# scarab-trigger-shield-bb.net
KiCad netlist of a schematic drawn in EAGLE
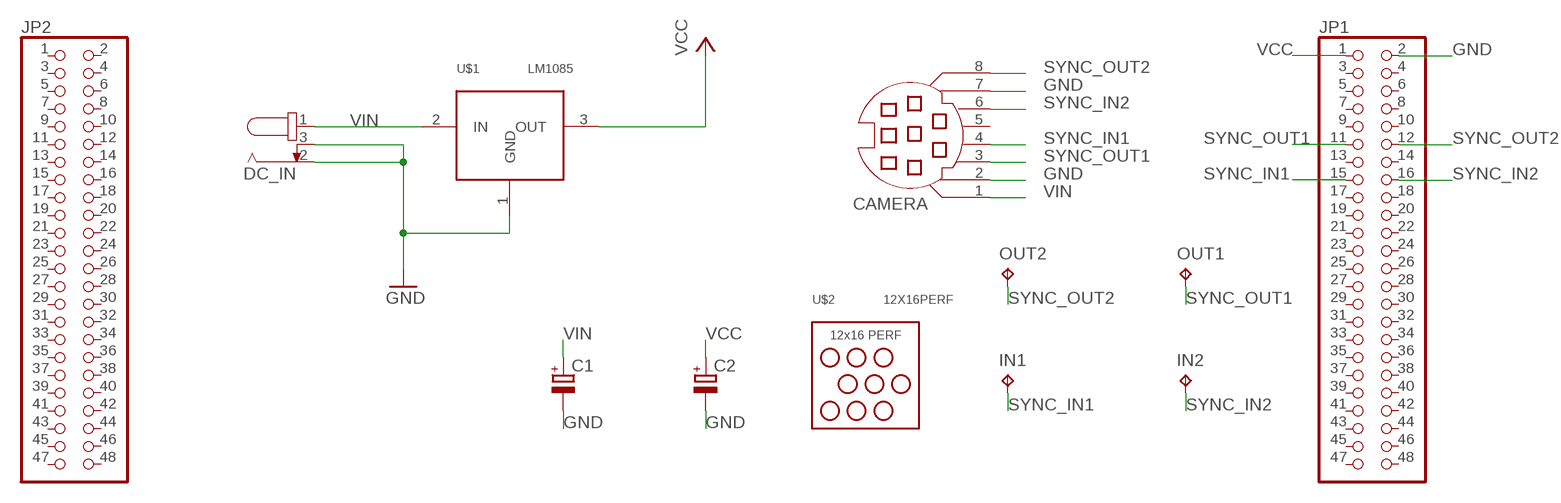
[diagram p0: schematic, sheet 1]

(export (version "E")
  (design (tool "Eeschema 10.0.6"))
  (components
    (comp (ref "C1")
      (value "CPOL-EUCT7343")
      (footprint "eagle-import:CT7343")
      (libsource (lib "eagle-import") (part "CPOL-EUCT7343"))
    )
    (comp (ref "C2")
      (value "CPOL-EUCT7343")
      (footprint "eagle-import:CT7343")
      (libsource (lib "eagle-import") (part "CPOL-EUCT7343"))
    )
    (comp (ref "CAMERA")
      (value "MD08SS")
      (footprint "eagle-import:MDIN08SS")
      (libsource (lib "eagle-import") (part "MD08SS"))
    )
    (comp (ref "DC_IN")
      (value "694106105102")
      (footprint "eagle-import:694106105102")
      (libsource (lib "eagle-import") (part "694106105102"))
    )
    (comp (ref "IN1")
      (value "TPTP20R")
      (footprint "eagle-import:TP20R")
      (libsource (lib "eagle-import") (part "TPTP20R"))
    )
    (comp (ref "IN2")
      (value "TPTP20R")
      (footprint "eagle-import:TP20R")
      (libsource (lib "eagle-import") (part "TPTP20R"))
    )
    (comp (ref "JP1")
      (value "PINHD-2X24")
      (footprint "eagle-import:2X24")
      (libsource (lib "eagle-import") (part "PINHD-2X24"))
    )
    (comp (ref "JP2")
      (value "PINHD-2X24")
      (footprint "eagle-import:2X24")
      (libsource (lib "eagle-import") (part "PINHD-2X24"))
    )
    (comp (ref "OUT1")
      (value "TPTP20R")
      (footprint "eagle-import:TP20R")
      (libsource (lib "eagle-import") (part "TPTP20R"))
    )
    (comp (ref "OUT2")
      (value "TPTP20R")
      (footprint "eagle-import:TP20R")
      (libsource (lib "eagle-import") (part "TPTP20R"))
    )
    (comp (ref "U$1")
      (value "LM1085")
      (footprint "eagle-import:TO263")
      (libsource (lib "eagle-import") (part "LM1085"))
    )
    (comp (ref "U$2")
      (value "12X16PERF")
      (footprint "eagle-import:PERF-GRID")
      (libsource (lib "eagle-import") (part "12X16PERF"))
    )
  )
  (nets
    (net (code "1") (name "/SYNC_IN1") (class "Default")
      (node (ref "CAMERA") (pin "4") (pinfunction "4_4") (pintype "passive"))
      (node (ref "IN1") (pin "TP") (pinfunction "TP_TP") (pintype "input"))
      (node (ref "JP1") (pin "15") (pinfunction "15_15") (pintype "passive"))
    )
    (net (code "2") (name "/SYNC_IN2") (class "Default")
      (node (ref "CAMERA") (pin "6") (pinfunction "6_6") (pintype "passive"))
      (node (ref "IN2") (pin "TP") (pinfunction "TP_TP") (pintype "input"))
      (node (ref "JP1") (pin "16") (pinfunction "16_16") (pintype "passive"))
    )
    (net (code "3") (name "/SYNC_OUT1") (class "Default")
      (node (ref "CAMERA") (pin "3") (pinfunction "3_3") (pintype "passive"))
      (node (ref "JP1") (pin "11") (pinfunction "11_11") (pintype "passive"))
      (node (ref "OUT1") (pin "TP") (pinfunction "TP_TP") (pintype "input"))
    )
    (net (code "4") (name "/SYNC_OUT2") (class "Default")
      (node (ref "CAMERA") (pin "8") (pinfunction "8_8") (pintype "passive"))
      (node (ref "JP1") (pin "12") (pinfunction "12_12") (pintype "passive"))
      (node (ref "OUT2") (pin "TP") (pinfunction "TP_TP") (pintype "input"))
    )
    (net (code "5") (name "/VIN") (class "Default")
      (node (ref "C1") (pin "+") (pinfunction "+_+") (pintype "passive"))
      (node (ref "CAMERA") (pin "1") (pinfunction "1_1") (pintype "passive"))
      (node (ref "DC_IN") (pin "1") (pinfunction "1_1") (pintype "passive"))
      (node (ref "U$1") (pin "2") (pinfunction "IN_2") (pintype "bidirectional"))
    )
    (net (code "6") (name "GND") (class "Default")
      (node (ref "C1") (pin "-") (pinfunction "-_-") (pintype "passive"))
      (node (ref "C2") (pin "-") (pinfunction "-_-") (pintype "passive"))
      (node (ref "CAMERA") (pin "2") (pinfunction "2_2") (pintype "passive"))
      (node (ref "CAMERA") (pin "7") (pinfunction "7_7") (pintype "passive"))
      (node (ref "DC_IN") (pin "2") (pinfunction "2_2") (pintype "passive"))
      (node (ref "DC_IN") (pin "3") (pinfunction "3_3") (pintype "passive"))
      (node (ref "JP1") (pin "2") (pinfunction "2_2") (pintype "passive"))
      (node (ref "U$1") (pin "1") (pinfunction "GND_1") (pintype "bidirectional"))
    )
    (net (code "7") (name "VCC") (class "Default")
      (node (ref "C2") (pin "+") (pinfunction "+_+") (pintype "passive"))
      (node (ref "JP1") (pin "1") (pinfunction "1_1") (pintype "passive"))
      (node (ref "U$1") (pin "3") (pinfunction "OUT_3") (pintype "bidirectional"))
    )
    (net (code "8") (name "unconnected-(CAMERA-Pad5)") (class "Default")
      (node (ref "CAMERA") (pin "5") (pinfunction "5_5") (pintype "passive"))
    )
    (net (code "9") (name "unconnected-(JP1-Pad3)") (class "Default")
      (node (ref "JP1") (pin "3") (pinfunction "3_3") (pintype "passive"))
    )
    (net (code "10") (name "unconnected-(JP1-Pad4)") (class "Default")
      (node (ref "JP1") (pin "4") (pinfunction "4_4") (pintype "passive"))
    )
    (net (code "11") (name "unconnected-(JP1-Pad5)") (class "Default")
      (node (ref "JP1") (pin "5") (pinfunction "5_5") (pintype "passive"))
    )
    (net (code "12") (name "unconnected-(JP1-Pad6)") (class "Default")
      (node (ref "JP1") (pin "6") (pinfunction "6_6") (pintype "passive"))
    )
    (net (code "13") (name "unconnected-(JP1-Pad7)") (class "Default")
      (node (ref "JP1") (pin "7") (pinfunction "7_7") (pintype "passive"))
    )
    (net (code "14") (name "unconnected-(JP1-Pad8)") (class "Default")
      (node (ref "JP1") (pin "8") (pinfunction "8_8") (pintype "passive"))
    )
    (net (code "15") (name "unconnected-(JP1-Pad9)") (class "Default")
      (node (ref "JP1") (pin "9") (pinfunction "9_9") (pintype "passive"))
    )
    (net (code "16") (name "unconnected-(JP1-Pad10)") (class "Default")
      (node (ref "JP1") (pin "10") (pinfunction "10_10") (pintype "passive"))
    )
    (net (code "17") (name "unconnected-(JP1-Pad13)") (class "Default")
      (node (ref "JP1") (pin "13") (pinfunction "13_13") (pintype "passive"))
    )
    (net (code "18") (name "unconnected-(JP1-Pad14)") (class "Default")
      (node (ref "JP1") (pin "14") (pinfunction "14_14") (pintype "passive"))
    )
    (net (code "19") (name "unconnected-(JP1-Pad17)") (class "Default")
      (node (ref "JP1") (pin "17") (pinfunction "17_17") (pintype "passive"))
    )
    (net (code "20") (name "unconnected-(JP1-Pad18)") (class "Default")
      (node (ref "JP1") (pin "18") (pinfunction "18_18") (pintype "passive"))
    )
    (net (code "21") (name "unconnected-(JP1-Pad19)") (class "Default")
      (node (ref "JP1") (pin "19") (pinfunction "19_19") (pintype "passive"))
    )
    (net (code "22") (name "unconnected-(JP1-Pad20)") (class "Default")
      (node (ref "JP1") (pin "20") (pinfunction "20_20") (pintype "passive"))
    )
    (net (code "23") (name "unconnected-(JP1-Pad21)") (class "Default")
      (node (ref "JP1") (pin "21") (pinfunction "21_21") (pintype "passive"))
    )
    (net (code "24") (name "unconnected-(JP1-Pad22)") (class "Default")
      (node (ref "JP1") (pin "22") (pinfunction "22_22") (pintype "passive"))
    )
    (net (code "25") (name "unconnected-(JP1-Pad23)") (class "Default")
      (node (ref "JP1") (pin "23") (pinfunction "23_23") (pintype "passive"))
    )
    (net (code "26") (name "unconnected-(JP1-Pad24)") (class "Default")
      (node (ref "JP1") (pin "24") (pinfunction "24_24") (pintype "passive"))
    )
    (net (code "27") (name "unconnected-(JP1-Pad25)") (class "Default")
      (node (ref "JP1") (pin "25") (pinfunction "25_25") (pintype "passive"))
    )
    (net (code "28") (name "unconnected-(JP1-Pad26)") (class "Default")
      (node (ref "JP1") (pin "26") (pinfunction "26_26") (pintype "passive"))
    )
    (net (code "29") (name "unconnected-(JP1-Pad27)") (class "Default")
      (node (ref "JP1") (pin "27") (pinfunction "27_27") (pintype "passive"))
    )
    (net (code "30") (name "unconnected-(JP1-Pad28)") (class "Default")
      (node (ref "JP1") (pin "28") (pinfunction "28_28") (pintype "passive"))
    )
    (net (code "31") (name "unconnected-(JP1-Pad29)") (class "Default")
      (node (ref "JP1") (pin "29") (pinfunction "29_29") (pintype "passive"))
    )
    (net (code "32") (name "unconnected-(JP1-Pad30)") (class "Default")
      (node (ref "JP1") (pin "30") (pinfunction "30_30") (pintype "passive"))
    )
    (net (code "33") (name "unconnected-(JP1-Pad31)") (class "Default")
      (node (ref "JP1") (pin "31") (pinfunction "31_31") (pintype "passive"))
    )
    (net (code "34") (name "unconnected-(JP1-Pad32)") (class "Default")
      (node (ref "JP1") (pin "32") (pinfunction "32_32") (pintype "passive"))
    )
    (net (code "35") (name "unconnected-(JP1-Pad33)") (class "Default")
      (node (ref "JP1") (pin "33") (pinfunction "33_33") (pintype "passive"))
    )
    (net (code "36") (name "unconnected-(JP1-Pad34)") (class "Default")
      (node (ref "JP1") (pin "34") (pinfunction "34_34") (pintype "passive"))
    )
    (net (code "37") (name "unconnected-(JP1-Pad35)") (class "Default")
      (node (ref "JP1") (pin "35") (pinfunction "35_35") (pintype "passive"))
    )
    (net (code "38") (name "unconnected-(JP1-Pad36)") (class "Default")
      (node (ref "JP1") (pin "36") (pinfunction "36_36") (pintype "passive"))
    )
    (net (code "39") (name "unconnected-(JP1-Pad37)") (class "Default")
      (node (ref "JP1") (pin "37") (pinfunction "37_37") (pintype "passive"))
    )
    (net (code "40") (name "unconnected-(JP1-Pad38)") (class "Default")
      (node (ref "JP1") (pin "38") (pinfunction "38_38") (pintype "passive"))
    )
    (net (code "41") (name "unconnected-(JP1-Pad39)") (class "Default")
      (node (ref "JP1") (pin "39") (pinfunction "39_39") (pintype "passive"))
    )
    (net (code "42") (name "unconnected-(JP1-Pad40)") (class "Default")
      (node (ref "JP1") (pin "40") (pinfunction "40_40") (pintype "passive"))
    )
    (net (code "43") (name "unconnected-(JP1-Pad41)") (class "Default")
      (node (ref "JP1") (pin "41") (pinfunction "41_41") (pintype "passive"))
    )
    (net (code "44") (name "unconnected-(JP1-Pad42)") (class "Default")
      (node (ref "JP1") (pin "42") (pinfunction "42_42") (pintype "passive"))
    )
    (net (code "45") (name "unconnected-(JP1-Pad43)") (class "Default")
      (node (ref "JP1") (pin "43") (pinfunction "43_43") (pintype "passive"))
    )
    (net (code "46") (name "unconnected-(JP1-Pad44)") (class "Default")
      (node (ref "JP1") (pin "44") (pinfunction "44_44") (pintype "passive"))
    )
    (net (code "47") (name "unconnected-(JP1-Pad45)") (class "Default")
      (node (ref "JP1") (pin "45") (pinfunction "45_45") (pintype "passive"))
    )
    (net (code "48") (name "unconnected-(JP1-Pad46)") (class "Default")
      (node (ref "JP1") (pin "46") (pinfunction "46_46") (pintype "passive"))
    )
    (net (code "49") (name "unconnected-(JP1-Pad47)") (class "Default")
      (node (ref "JP1") (pin "47") (pinfunction "47_47") (pintype "passive"))
    )
    (net (code "50") (name "unconnected-(JP1-Pad48)") (class "Default")
      (node (ref "JP1") (pin "48") (pinfunction "48_48") (pintype "passive"))
    )
    (net (code "51") (name "unconnected-(JP2-Pad1)") (class "Default")
      (node (ref "JP2") (pin "1") (pinfunction "1_1") (pintype "passive"))
    )
    (net (code "52") (name "unconnected-(JP2-Pad2)") (class "Default")
      (node (ref "JP2") (pin "2") (pinfunction "2_2") (pintype "passive"))
    )
    (net (code "53") (name "unconnected-(JP2-Pad3)") (class "Default")
      (node (ref "JP2") (pin "3") (pinfunction "3_3") (pintype "passive"))
    )
    (net (code "54") (name "unconnected-(JP2-Pad4)") (class "Default")
      (node (ref "JP2") (pin "4") (pinfunction "4_4") (pintype "passive"))
    )
    (net (code "55") (name "unconnected-(JP2-Pad5)") (class "Default")
      (node (ref "JP2") (pin "5") (pinfunction "5_5") (pintype "passive"))
    )
    (net (code "56") (name "unconnected-(JP2-Pad6)") (class "Default")
      (node (ref "JP2") (pin "6") (pinfunction "6_6") (pintype "passive"))
    )
    (net (code "57") (name "unconnected-(JP2-Pad7)") (class "Default")
      (node (ref "JP2") (pin "7") (pinfunction "7_7") (pintype "passive"))
    )
    (net (code "58") (name "unconnected-(JP2-Pad8)") (class "Default")
      (node (ref "JP2") (pin "8") (pinfunction "8_8") (pintype "passive"))
    )
    (net (code "59") (name "unconnected-(JP2-Pad9)") (class "Default")
      (node (ref "JP2") (pin "9") (pinfunction "9_9") (pintype "passive"))
    )
    (net (code "60") (name "unconnected-(JP2-Pad10)") (class "Default")
      (node (ref "JP2") (pin "10") (pinfunction "10_10") (pintype "passive"))
    )
    (net (code "61") (name "unconnected-(JP2-Pad11)") (class "Default")
      (node (ref "JP2") (pin "11") (pinfunction "11_11") (pintype "passive"))
    )
    (net (code "62") (name "unconnected-(JP2-Pad12)") (class "Default")
      (node (ref "JP2") (pin "12") (pinfunction "12_12") (pintype "passive"))
    )
    (net (code "63") (name "unconnected-(JP2-Pad13)") (class "Default")
      (node (ref "JP2") (pin "13") (pinfunction "13_13") (pintype "passive"))
    )
    (net (code "64") (name "unconnected-(JP2-Pad14)") (class "Default")
      (node (ref "JP2") (pin "14") (pinfunction "14_14") (pintype "passive"))
    )
    (net (code "65") (name "unconnected-(JP2-Pad15)") (class "Default")
      (node (ref "JP2") (pin "15") (pinfunction "15_15") (pintype "passive"))
    )
    (net (code "66") (name "unconnected-(JP2-Pad16)") (class "Default")
      (node (ref "JP2") (pin "16") (pinfunction "16_16") (pintype "passive"))
    )
    (net (code "67") (name "unconnected-(JP2-Pad17)") (class "Default")
      (node (ref "JP2") (pin "17") (pinfunction "17_17") (pintype "passive"))
    )
    (net (code "68") (name "unconnected-(JP2-Pad18)") (class "Default")
      (node (ref "JP2") (pin "18") (pinfunction "18_18") (pintype "passive"))
    )
    (net (code "69") (name "unconnected-(JP2-Pad19)") (class "Default")
      (node (ref "JP2") (pin "19") (pinfunction "19_19") (pintype "passive"))
    )
    (net (code "70") (name "unconnected-(JP2-Pad20)") (class "Default")
      (node (ref "JP2") (pin "20") (pinfunction "20_20") (pintype "passive"))
    )
    (net (code "71") (name "unconnected-(JP2-Pad21)") (class "Default")
      (node (ref "JP2") (pin "21") (pinfunction "21_21") (pintype "passive"))
    )
    (net (code "72") (name "unconnected-(JP2-Pad22)") (class "Default")
      (node (ref "JP2") (pin "22") (pinfunction "22_22") (pintype "passive"))
    )
    (net (code "73") (name "unconnected-(JP2-Pad23)") (class "Default")
      (node (ref "JP2") (pin "23") (pinfunction "23_23") (pintype "passive"))
    )
    (net (code "74") (name "unconnected-(JP2-Pad24)") (class "Default")
      (node (ref "JP2") (pin "24") (pinfunction "24_24") (pintype "passive"))
    )
    (net (code "75") (name "unconnected-(JP2-Pad25)") (class "Default")
      (node (ref "JP2") (pin "25") (pinfunction "25_25") (pintype "passive"))
    )
    (net (code "76") (name "unconnected-(JP2-Pad26)") (class "Default")
      (node (ref "JP2") (pin "26") (pinfunction "26_26") (pintype "passive"))
    )
    (net (code "77") (name "unconnected-(JP2-Pad27)") (class "Default")
      (node (ref "JP2") (pin "27") (pinfunction "27_27") (pintype "passive"))
    )
    (net (code "78") (name "unconnected-(JP2-Pad28)") (class "Default")
      (node (ref "JP2") (pin "28") (pinfunction "28_28") (pintype "passive"))
    )
    (net (code "79") (name "unconnected-(JP2-Pad29)") (class "Default")
      (node (ref "JP2") (pin "29") (pinfunction "29_29") (pintype "passive"))
    )
    (net (code "80") (name "unconnected-(JP2-Pad30)") (class "Default")
      (node (ref "JP2") (pin "30") (pinfunction "30_30") (pintype "passive"))
    )
    (net (code "81") (name "unconnected-(JP2-Pad31)") (class "Default")
      (node (ref "JP2") (pin "31") (pinfunction "31_31") (pintype "passive"))
    )
    (net (code "82") (name "unconnected-(JP2-Pad32)") (class "Default")
      (node (ref "JP2") (pin "32") (pinfunction "32_32") (pintype "passive"))
    )
    (net (code "83") (name "unconnected-(JP2-Pad33)") (class "Default")
      (node (ref "JP2") (pin "33") (pinfunction "33_33") (pintype "passive"))
    )
    (net (code "84") (name "unconnected-(JP2-Pad34)") (class "Default")
      (node (ref "JP2") (pin "34") (pinfunction "34_34") (pintype "passive"))
    )
    (net (code "85") (name "unconnected-(JP2-Pad35)") (class "Default")
      (node (ref "JP2") (pin "35") (pinfunction "35_35") (pintype "passive"))
    )
    (net (code "86") (name "unconnected-(JP2-Pad36)") (class "Default")
      (node (ref "JP2") (pin "36") (pinfunction "36_36") (pintype "passive"))
    )
    (net (code "87") (name "unconnected-(JP2-Pad37)") (class "Default")
      (node (ref "JP2") (pin "37") (pinfunction "37_37") (pintype "passive"))
    )
    (net (code "88") (name "unconnected-(JP2-Pad38)") (class "Default")
      (node (ref "JP2") (pin "38") (pinfunction "38_38") (pintype "passive"))
    )
    (net (code "89") (name "unconnected-(JP2-Pad39)") (class "Default")
      (node (ref "JP2") (pin "39") (pinfunction "39_39") (pintype "passive"))
    )
    (net (code "90") (name "unconnected-(JP2-Pad40)") (class "Default")
      (node (ref "JP2") (pin "40") (pinfunction "40_40") (pintype "passive"))
    )
    (net (code "91") (name "unconnected-(JP2-Pad41)") (class "Default")
      (node (ref "JP2") (pin "41") (pinfunction "41_41") (pintype "passive"))
    )
    (net (code "92") (name "unconnected-(JP2-Pad42)") (class "Default")
      (node (ref "JP2") (pin "42") (pinfunction "42_42") (pintype "passive"))
    )
    (net (code "93") (name "unconnected-(JP2-Pad43)") (class "Default")
      (node (ref "JP2") (pin "43") (pinfunction "43_43") (pintype "passive"))
    )
    (net (code "94") (name "unconnected-(JP2-Pad44)") (class "Default")
      (node (ref "JP2") (pin "44") (pinfunction "44_44") (pintype "passive"))
    )
    (net (code "95") (name "unconnected-(JP2-Pad45)") (class "Default")
      (node (ref "JP2") (pin "45") (pinfunction "45_45") (pintype "passive"))
    )
    (net (code "96") (name "unconnected-(JP2-Pad46)") (class "Default")
      (node (ref "JP2") (pin "46") (pinfunction "46_46") (pintype "passive"))
    )
    (net (code "97") (name "unconnected-(JP2-Pad47)") (class "Default")
      (node (ref "JP2") (pin "47") (pinfunction "47_47") (pintype "passive"))
    )
    (net (code "98") (name "unconnected-(JP2-Pad48)") (class "Default")
      (node (ref "JP2") (pin "48") (pinfunction "48_48") (pintype "passive"))
    )
  )
)
